# sklpf.net
KiCad netlist of a schematic drawn in EAGLE
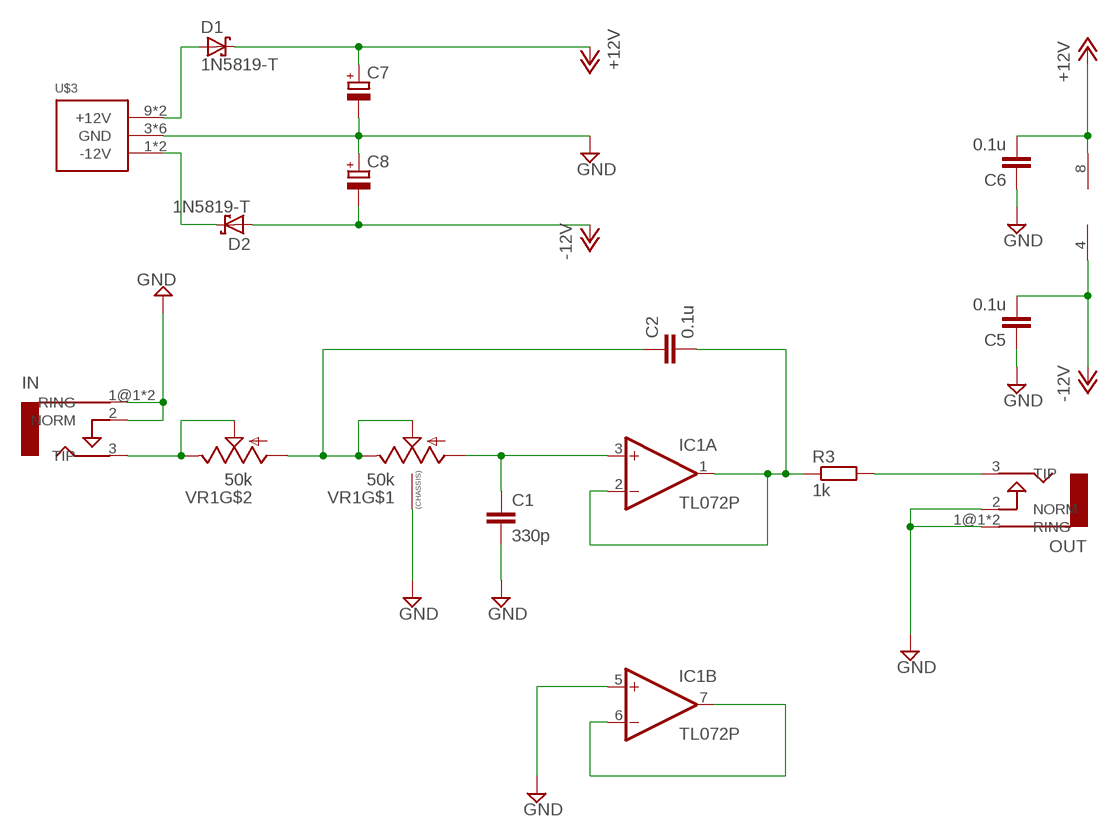
[diagram p0: schematic, sheet 1]

(export (version "E")
  (design (tool "Eeschema 10.0.6"))
  (components
    (comp (ref "C1")
      (value "330p")
      (footprint "eagle-import:C025-025X050")
      (libsource (lib "eagle-import") (part "C-EU025-025X050"))
    )
    (comp (ref "C2")
      (value "0.1u")
      (footprint "eagle-import:C050-025X075")
      (libsource (lib "eagle-import") (part "C-EU050-025X075"))
    )
    (comp (ref "C5")
      (value "0.1u")
      (footprint "eagle-import:C025-025X050")
      (libsource (lib "eagle-import") (part "C-EU025-025X050"))
    )
    (comp (ref "C6")
      (value "0.1u")
      (footprint "eagle-import:C025-025X050")
      (libsource (lib "eagle-import") (part "C-EU025-025X050"))
    )
    (comp (ref "C7")
      (value "CPOL-EUE2,5-6E")
      (footprint "eagle-import:E2,5-6E")
      (libsource (lib "eagle-import") (part "CPOL-EUE2,5-6E"))
    )
    (comp (ref "C8")
      (value "CPOL-EUE2,5-6E")
      (footprint "eagle-import:E2,5-6E")
      (libsource (lib "eagle-import") (part "CPOL-EUE2,5-6E"))
    )
    (comp (ref "D1")
      (value "1N5819-T")
      (footprint "eagle-import:DO41-7.6")
      (libsource (lib "eagle-import") (part "1N5819-T"))
    )
    (comp (ref "D2")
      (value "1N5819-T")
      (footprint "eagle-import:DO41-7.6")
      (libsource (lib "eagle-import") (part "1N5819-T"))
    )
    (comp (ref "IC1")
      (value "TL072P")
      (footprint "eagle-import:DIL08")
      (libsource (lib "eagle-import") (part "TL072P"))
    )
    (comp (ref "IN")
      (value "AUDIO-JACKERTHENVAR")
      (footprint "eagle-import:ERTHENVAR-JACK")
      (libsource (lib "eagle-import") (part "AUDIO-JACKERTHENVAR"))
    )
    (comp (ref "OUT")
      (value "AUDIO-JACKERTHENVAR")
      (footprint "eagle-import:ERTHENVAR-JACK")
      (libsource (lib "eagle-import") (part "AUDIO-JACKERTHENVAR"))
    )
    (comp (ref "R3")
      (value "1k")
      (footprint "eagle-import:0207_2V")
      (libsource (lib "eagle-import") (part "R-EU_0207/2V"))
    )
    (comp (ref "U$3")
      (value "POWER_SIMPLE10")
      (footprint "eagle-import:POWER_10")
      (libsource (lib "eagle-import") (part "POWER_SIMPLE10"))
    )
    (comp (ref "VR1")
      (value "50k")
      (footprint "eagle-import:DUAL_9MM_SNAP-IN_POT")
      (libsource (lib "eagle-import") (part "ALPHA-9MM-DUALPOT"))
    )
  )
  (nets
    (net (code "1") (name "+12V") (class "Default")
      (node (ref "C6") (pin "2") (pinfunction "2_2") (pintype "passive"))
      (node (ref "C7") (pin "+") (pinfunction "+_+") (pintype "passive"))
      (node (ref "D1") (pin "C") (pinfunction "C_C") (pintype "passive"))
      (node (ref "IC1") (pin "8") (pinfunction "V+_8") (pintype "power_in"))
    )
    (net (code "2") (name "-12V") (class "Default")
      (node (ref "C5") (pin "2") (pinfunction "2_2") (pintype "passive"))
      (node (ref "C8") (pin "-") (pinfunction "-_-") (pintype "passive"))
      (node (ref "D2") (pin "A") (pinfunction "A_A") (pintype "passive"))
      (node (ref "IC1") (pin "4") (pinfunction "V-_4") (pintype "power_in"))
    )
    (net (code "3") (name "GND") (class "Default")
      (node (ref "C1") (pin "2") (pinfunction "2_2") (pintype "passive"))
      (node (ref "C5") (pin "1") (pinfunction "1_1") (pintype "passive"))
      (node (ref "C6") (pin "1") (pinfunction "1_1") (pintype "passive"))
      (node (ref "C7") (pin "-") (pinfunction "-_-") (pintype "passive"))
      (node (ref "C8") (pin "+") (pinfunction "+_+") (pintype "passive"))
      (node (ref "IC1") (pin "5") (pinfunction "+IN_5") (pintype "input"))
      (node (ref "IN") (pin "1@1") (pinfunction "RING_1@1") (pintype "bidirectional"))
      (node (ref "IN") (pin "1@2") (pinfunction "RING_1@2") (pintype "bidirectional"))
      (node (ref "IN") (pin "2") (pinfunction "NORM_2") (pintype "bidirectional"))
      (node (ref "OUT") (pin "1@1") (pinfunction "RING_1@1") (pintype "bidirectional"))
      (node (ref "OUT") (pin "1@2") (pinfunction "RING_1@2") (pintype "bidirectional"))
      (node (ref "OUT") (pin "2") (pinfunction "NORM_2") (pintype "bidirectional"))
      (node (ref "U$3") (pin "3") (pinfunction "GND_3") (pintype "bidirectional"))
      (node (ref "U$3") (pin "4") (pinfunction "GND_4") (pintype "bidirectional"))
      (node (ref "U$3") (pin "5") (pinfunction "GND_5") (pintype "bidirectional"))
      (node (ref "U$3") (pin "6") (pinfunction "GND_6") (pintype "bidirectional"))
      (node (ref "U$3") (pin "7") (pinfunction "GND_7") (pintype "bidirectional"))
      (node (ref "U$3") (pin "8") (pinfunction "GND_8") (pintype "bidirectional"))
      (node (ref "VR1") (pin "CHASSIS1") (pinfunction "P$1_CHASSIS1") (pintype "passive"))
      (node (ref "VR1") (pin "CHASSIS2") (pinfunction "P$1_CHASSIS2") (pintype "passive"))
    )
    (net (code "4") (name "Net-(D1-PadA)") (class "Default")
      (node (ref "D1") (pin "A") (pinfunction "A_A") (pintype "passive"))
      (node (ref "U$3") (pin "10") (pinfunction "+12V_10") (pintype "bidirectional"))
      (node (ref "U$3") (pin "9") (pinfunction "+12V_9") (pintype "bidirectional"))
    )
    (net (code "5") (name "Net-(D2-PadC)") (class "Default")
      (node (ref "D2") (pin "C") (pinfunction "C_C") (pintype "passive"))
      (node (ref "U$3") (pin "1") (pinfunction "-12V_1") (pintype "bidirectional"))
      (node (ref "U$3") (pin "2") (pinfunction "-12V_2") (pintype "bidirectional"))
    )
    (net (code "6") (name "Net-(IC1A-+IN)") (class "Default")
      (node (ref "C1") (pin "1") (pinfunction "1_1") (pintype "passive"))
      (node (ref "IC1") (pin "3") (pinfunction "+IN_3") (pintype "input"))
      (node (ref "VR1") (pin "1") (pinfunction "A_1") (pintype "passive"))
    )
    (net (code "7") (name "Net-(IC1A--IN)") (class "Default")
      (node (ref "C2") (pin "2") (pinfunction "2_2") (pintype "passive"))
      (node (ref "IC1") (pin "1") (pinfunction "OUT_1") (pintype "output"))
      (node (ref "IC1") (pin "2") (pinfunction "-IN_2") (pintype "input"))
      (node (ref "R3") (pin "1") (pinfunction "1_1") (pintype "passive"))
    )
    (net (code "8") (name "Net-(IC1B--IN)") (class "Default")
      (node (ref "IC1") (pin "6") (pinfunction "-IN_6") (pintype "input"))
      (node (ref "IC1") (pin "7") (pinfunction "OUT_7") (pintype "output"))
    )
    (net (code "9") (name "Net-(IN-TIP)") (class "Default")
      (node (ref "IN") (pin "3") (pinfunction "TIP_3") (pintype "bidirectional"))
      (node (ref "VR1") (pin "2B") (pinfunction "S_2B") (pintype "passive"))
      (node (ref "VR1") (pin "3B") (pinfunction "E_3B") (pintype "passive"))
    )
    (net (code "10") (name "Net-(OUT-TIP)") (class "Default")
      (node (ref "OUT") (pin "3") (pinfunction "TIP_3") (pintype "bidirectional"))
      (node (ref "R3") (pin "2") (pinfunction "2_2") (pintype "passive"))
    )
    (net (code "11") (name "Net-(VR1A-E)") (class "Default")
      (node (ref "C2") (pin "1") (pinfunction "1_1") (pintype "passive"))
      (node (ref "VR1") (pin "1B") (pinfunction "A_1B") (pintype "passive"))
      (node (ref "VR1") (pin "2") (pinfunction "S_2") (pintype "passive"))
      (node (ref "VR1") (pin "3") (pinfunction "E_3") (pintype "passive"))
    )
  )
)
